# project_9.net
KiCad netlist of a schematic drawn in Altium Designer
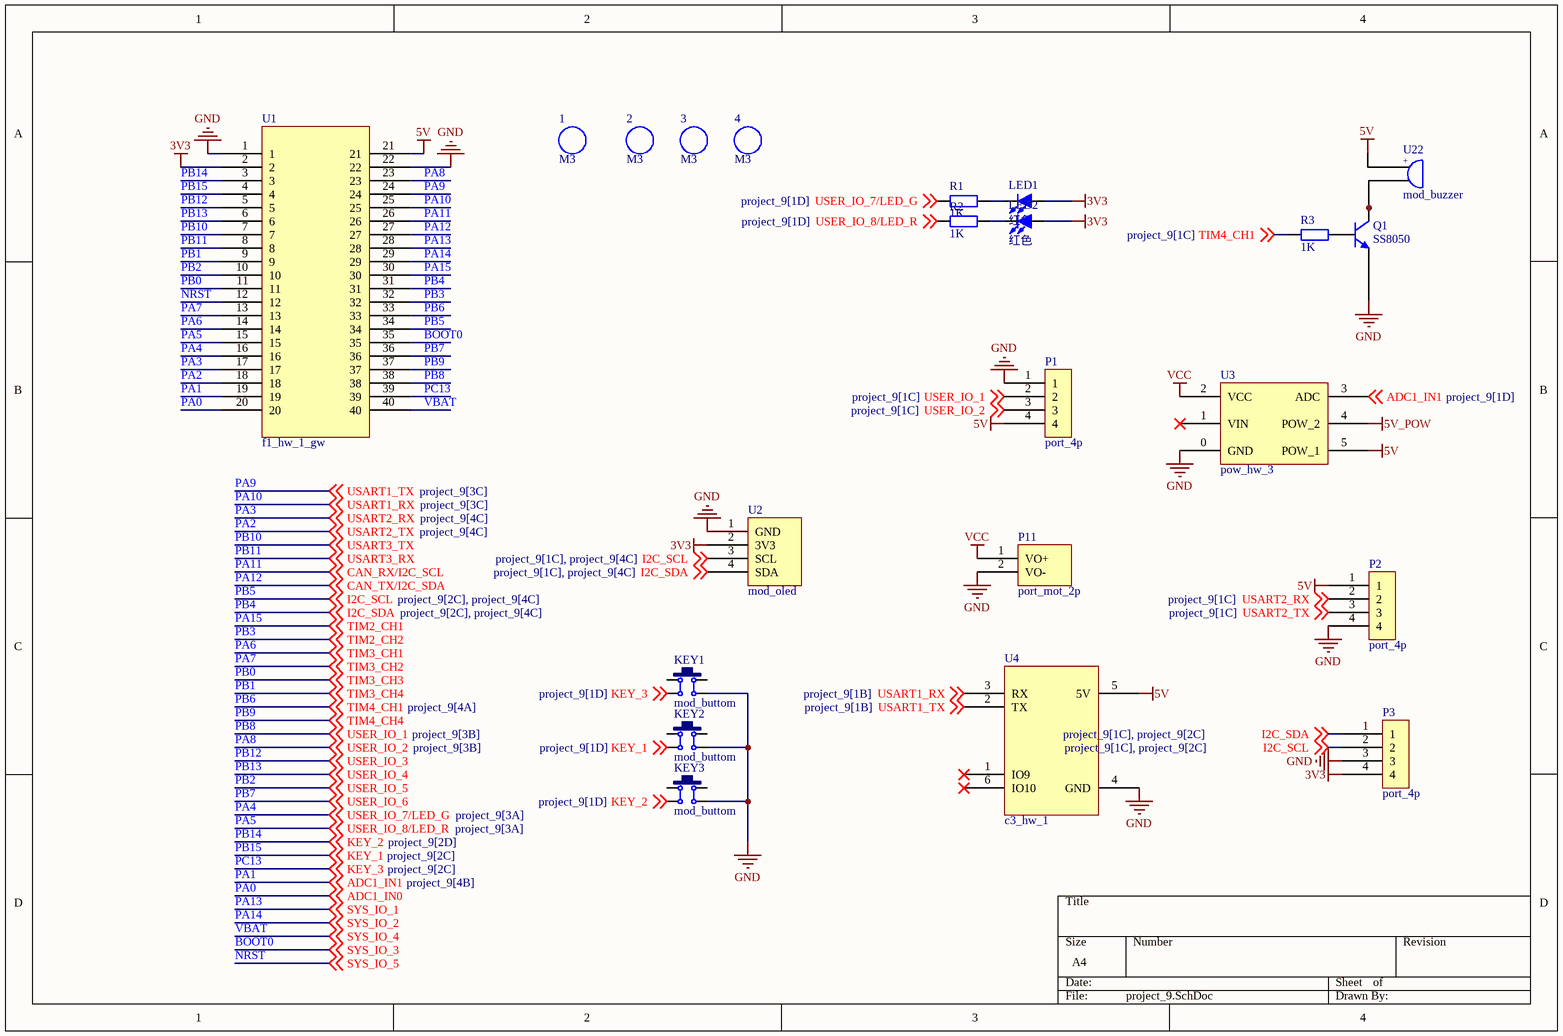
[diagram p0: project_9.SchDoc]

(export (version "E")
  (design (tool "Eeschema 10.0.6"))
  (components
    (comp (ref "1")
      (value "M3")
      (footprint "M3 125X200")
      (description "m3铜柱孔")
      (fields (field (name "版权归属") "源创客"))
      (libsource (lib "userLib") (part "prot_m3"))
    )
    (comp (ref "2")
      (value "M3")
      (footprint "M3 125X200")
      (description "m3铜柱孔")
      (fields (field (name "版权归属") "源创客"))
      (libsource (lib "userLib") (part "prot_m3"))
    )
    (comp (ref "3")
      (value "M3")
      (footprint "M3 125X200")
      (description "m3铜柱孔")
      (fields (field (name "版权归属") "源创客"))
      (libsource (lib "userLib") (part "prot_m3"))
    )
    (comp (ref "4")
      (value "M3")
      (footprint "M3 125X200")
      (description "m3铜柱孔")
      (fields (field (name "版权归属") "源创客"))
      (libsource (lib "userLib") (part "prot_m3"))
    )
    (comp (ref "KEY1")
      (value "mod_buttom")
      (footprint "MOD_BUTTOM")
      (description "6*6*4.3按键")
      (libsource (lib "userLib") (part "mod_buttom"))
    )
    (comp (ref "KEY2")
      (value "mod_buttom")
      (footprint "MOD_BUTTOM")
      (description "6*6*4.3按键")
      (libsource (lib "userLib") (part "mod_buttom"))
    )
    (comp (ref "KEY3")
      (value "mod_buttom")
      (footprint "MOD_BUTTOM")
      (description "6*6*4.3按键")
      (libsource (lib "userLib") (part "mod_buttom"))
    )
    (comp (ref "LED1")
      (value "红色")
      (footprint "LED 3MM-B")
      (description "插件LED")
      (fields (field (name "版权归属") "源创客"))
      (libsource (lib "userLib") (part "mod_LED"))
    )
    (comp (ref "LED2")
      (value "红色")
      (footprint "LED 3MM-B")
      (description "插件LED")
      (fields (field (name "版权归属") "源创客"))
      (libsource (lib "userLib") (part "mod_LED"))
    )
    (comp (ref "P1")
      (value "port_4p")
      (footprint "MOD_ECHO(XH2.54)")
      (description "4P模块接口")
      (libsource (lib "userLib") (part "port_4p"))
    )
    (comp (ref "P2")
      (value "port_4p")
      (footprint "MOD_RS485")
      (description "4P模块接口")
      (libsource (lib "userLib") (part "port_4p"))
    )
    (comp (ref "P3")
      (value "port_4p")
      (footprint "MOD_TEMP")
      (description "4P模块接口")
      (libsource (lib "userLib") (part "port_4p"))
    )
    (comp (ref "P11")
      (value "port_mot_2p")
      (footprint "XH2.54_2P")
      (description "开环直流电机接口\r\nXH2.54弯排针2p")
      (libsource (lib "userLib") (part "port_mot_2p"))
    )
    (comp (ref "Q1")
      (value "SS8050")
      (footprint "SOT23-3L")
      (description "高频放大-NPN型")
      (fields (field (name "版权归属") "源创客"))
      (libsource (lib "5.1-三极管") (part "8050-SMD"))
    )
    (comp (ref "R1")
      (value "1K")
      (footprint "R 0603_L")
      (description "贴片电阻")
      (fields (field (name "版权归属") "源创客"))
      (libsource (lib "3.1-电阻") (part "R"))
    )
    (comp (ref "R2")
      (value "1K")
      (footprint "R 0603_L")
      (description "贴片电阻")
      (fields (field (name "版权归属") "源创客"))
      (libsource (lib "3.1-电阻") (part "R"))
    )
    (comp (ref "R3")
      (value "1K")
      (footprint "R 0603_L")
      (description "贴片电阻")
      (fields (field (name "版权归属") "源创客"))
      (libsource (lib "3.1-电阻") (part "R"))
    )
    (comp (ref "U1")
      (value "f1_hw_1_gw")
      (footprint "F1_HW_1_GW")
      (libsource (lib "userLib") (part "f1_hw_1_gw"))
    )
    (comp (ref "U2")
      (value "mod_oled")
      (footprint "MOD_OLED")
      (description "oled模块\r\n4p排母")
      (libsource (lib "userLib") (part "mod_oled"))
    )
    (comp (ref "U3") (value "pow_hw_3") (footprint "POW_HW_3") (libsource (lib "userLib") (part "pow_hw_3")))
    (comp (ref "U4")
      (value "c3_hw_1")
      (footprint "C3_HW_1")
      (description "ESP32C3蓝牙模块\r\n6p排母")
      (libsource (lib "userLib") (part "c3_hw_1"))
    )
    (comp (ref "U22")
      (value "mod_buzzer")
      (footprint "MOD_BUZZER")
      (description "有源蜂鸣器")
      (libsource (lib "userLib") (part "mod_buzzer"))
    )
  )
  (nets
    (net (code "1") (name "3V3") (class "Default")
      (node (ref "LED1") (pin "1") (pinfunction "A_1") (pintype "passive"))
      (node (ref "LED2") (pin "1") (pinfunction "A_1") (pintype "passive"))
      (node (ref "P3") (pin "4") (pinfunction "4_4") (pintype "passive"))
      (node (ref "U1") (pin "2") (pinfunction "2_2") (pintype "passive"))
      (node (ref "U2") (pin "2") (pinfunction "3V3_2") (pintype "passive"))
    )
    (net (code "2") (name "5V") (class "Default")
      (node (ref "P1") (pin "4") (pinfunction "4_4") (pintype "passive"))
      (node (ref "P2") (pin "1") (pinfunction "1_1") (pintype "passive"))
      (node (ref "U1") (pin "21") (pinfunction "21_21") (pintype "passive"))
      (node (ref "U22") (pin "1") (pinfunction "1_1") (pintype "passive"))
      (node (ref "U3") (pin "5") (pinfunction "POW_1_5") (pintype "passive"))
      (node (ref "U4") (pin "5") (pinfunction "5V_5") (pintype "passive"))
    )
    (net (code "3") (name "5V_POW") (class "Default")
      (node (ref "U3") (pin "4") (pinfunction "POW_2_4") (pintype "passive"))
    )
    (net (code "4") (name "ADC1_IN0") (class "Default")
      (node (ref "U1") (pin "20") (pinfunction "20_20") (pintype "passive"))
    )
    (net (code "5") (name "ADC1_IN1") (class "Default")
      (node (ref "U1") (pin "19") (pinfunction "19_19") (pintype "passive"))
      (node (ref "U3") (pin "3") (pinfunction "ADC_3") (pintype "passive"))
    )
    (net (code "6") (name "CAN_RX{slash}I2C_SCL") (class "Default")
      (node (ref "U1") (pin "26") (pinfunction "26_26") (pintype "passive"))
    )
    (net (code "7") (name "CAN_TX{slash}I2C_SDA") (class "Default")
      (node (ref "U1") (pin "27") (pinfunction "27_27") (pintype "passive"))
    )
    (net (code "8") (name "GND") (class "Default")
      (node (ref "KEY1") (pin "3") (pinfunction "3_3") (pintype "passive"))
      (node (ref "KEY2") (pin "3") (pinfunction "3_3") (pintype "passive"))
      (node (ref "KEY3") (pin "3") (pinfunction "3_3") (pintype "passive"))
      (node (ref "P1") (pin "1") (pinfunction "1_1") (pintype "passive"))
      (node (ref "P11") (pin "2") (pinfunction "VO-_2") (pintype "passive"))
      (node (ref "P2") (pin "4") (pinfunction "4_4") (pintype "passive"))
      (node (ref "P3") (pin "3") (pinfunction "3_3") (pintype "passive"))
      (node (ref "Q1") (pin "2") (pinfunction "E_2") (pintype "passive"))
      (node (ref "U1") (pin "1") (pinfunction "1_1") (pintype "passive"))
      (node (ref "U1") (pin "22") (pinfunction "22_22") (pintype "passive"))
      (node (ref "U2") (pin "1") (pinfunction "GND_1") (pintype "passive"))
      (node (ref "U3") (pin "0") (pinfunction "GND_0") (pintype "passive"))
      (node (ref "U4") (pin "4") (pinfunction "GND_4") (pintype "passive"))
    )
    (net (code "9") (name "I2C_SCL") (class "Default")
      (node (ref "P3") (pin "2") (pinfunction "2_2") (pintype "passive"))
      (node (ref "U1") (pin "34") (pinfunction "34_34") (pintype "passive"))
      (node (ref "U2") (pin "3") (pinfunction "SCL_3") (pintype "passive"))
    )
    (net (code "10") (name "I2C_SDA") (class "Default")
      (node (ref "P3") (pin "1") (pinfunction "1_1") (pintype "passive"))
      (node (ref "U1") (pin "31") (pinfunction "31_31") (pintype "passive"))
      (node (ref "U2") (pin "4") (pinfunction "SDA_4") (pintype "passive"))
    )
    (net (code "11") (name "KEY_1") (class "Default")
      (node (ref "KEY2") (pin "4") (pinfunction "4_4") (pintype "passive"))
      (node (ref "U1") (pin "4") (pinfunction "4_4") (pintype "passive"))
    )
    (net (code "12") (name "KEY_2") (class "Default")
      (node (ref "KEY3") (pin "4") (pinfunction "4_4") (pintype "passive"))
      (node (ref "U1") (pin "3") (pinfunction "3_3") (pintype "passive"))
    )
    (net (code "13") (name "KEY_3") (class "Default")
      (node (ref "KEY1") (pin "4") (pinfunction "4_4") (pintype "passive"))
      (node (ref "U1") (pin "39") (pinfunction "39_39") (pintype "passive"))
    )
    (net (code "14") (name "Net-(LED1-K)") (class "Default")
      (node (ref "LED1") (pin "2") (pinfunction "K_2") (pintype "passive"))
      (node (ref "R1") (pin "2") (pinfunction "2_2") (pintype "passive"))
    )
    (net (code "15") (name "Net-(LED2-K)") (class "Default")
      (node (ref "LED2") (pin "2") (pinfunction "K_2") (pintype "passive"))
      (node (ref "R2") (pin "2") (pinfunction "2_2") (pintype "passive"))
    )
    (net (code "16") (name "Net-(Q1-B)") (class "Default")
      (node (ref "Q1") (pin "1") (pinfunction "B_1") (pintype "passive"))
      (node (ref "R3") (pin "2") (pinfunction "2_2") (pintype "passive"))
    )
    (net (code "17") (name "Net-(Q1-C)") (class "Default")
      (node (ref "Q1") (pin "3") (pinfunction "C_3") (pintype "passive"))
      (node (ref "U22") (pin "2") (pinfunction "2_2") (pintype "passive"))
    )
    (net (code "18") (name "SYS_IO_1") (class "Default")
      (node (ref "U1") (pin "28") (pinfunction "28_28") (pintype "passive"))
    )
    (net (code "19") (name "SYS_IO_2") (class "Default")
      (node (ref "U1") (pin "29") (pinfunction "29_29") (pintype "passive"))
    )
    (net (code "20") (name "SYS_IO_3") (class "Default")
      (node (ref "U1") (pin "35") (pinfunction "35_35") (pintype "passive"))
    )
    (net (code "21") (name "SYS_IO_4") (class "Default")
      (node (ref "U1") (pin "40") (pinfunction "40_40") (pintype "passive"))
    )
    (net (code "22") (name "SYS_IO_5") (class "Default")
      (node (ref "U1") (pin "12") (pinfunction "12_12") (pintype "passive"))
    )
    (net (code "23") (name "TIM2_CH1") (class "Default")
      (node (ref "U1") (pin "30") (pinfunction "30_30") (pintype "passive"))
    )
    (net (code "24") (name "TIM2_CH2") (class "Default")
      (node (ref "U1") (pin "32") (pinfunction "32_32") (pintype "passive"))
    )
    (net (code "25") (name "TIM3_CH1") (class "Default")
      (node (ref "U1") (pin "14") (pinfunction "14_14") (pintype "passive"))
    )
    (net (code "26") (name "TIM3_CH2") (class "Default")
      (node (ref "U1") (pin "13") (pinfunction "13_13") (pintype "passive"))
    )
    (net (code "27") (name "TIM3_CH3") (class "Default")
      (node (ref "U1") (pin "11") (pinfunction "11_11") (pintype "passive"))
    )
    (net (code "28") (name "TIM3_CH4") (class "Default")
      (node (ref "U1") (pin "9") (pinfunction "9_9") (pintype "passive"))
    )
    (net (code "29") (name "TIM4_CH1") (class "Default")
      (node (ref "R3") (pin "1") (pinfunction "1_1") (pintype "passive"))
      (node (ref "U1") (pin "33") (pinfunction "33_33") (pintype "passive"))
    )
    (net (code "30") (name "TIM4_CH4") (class "Default")
      (node (ref "U1") (pin "37") (pinfunction "37_37") (pintype "passive"))
    )
    (net (code "31") (name "USART1_RX") (class "Default")
      (node (ref "U1") (pin "25") (pinfunction "25_25") (pintype "passive"))
      (node (ref "U4") (pin "3") (pinfunction "RX_3") (pintype "passive"))
    )
    (net (code "32") (name "USART1_TX") (class "Default")
      (node (ref "U1") (pin "24") (pinfunction "24_24") (pintype "passive"))
      (node (ref "U4") (pin "2") (pinfunction "TX_2") (pintype "passive"))
    )
    (net (code "33") (name "USART2_RX") (class "Default")
      (node (ref "P2") (pin "2") (pinfunction "2_2") (pintype "passive"))
      (node (ref "U1") (pin "17") (pinfunction "17_17") (pintype "passive"))
    )
    (net (code "34") (name "USART2_TX") (class "Default")
      (node (ref "P2") (pin "3") (pinfunction "3_3") (pintype "passive"))
      (node (ref "U1") (pin "18") (pinfunction "18_18") (pintype "passive"))
    )
    (net (code "35") (name "USART3_RX") (class "Default")
      (node (ref "U1") (pin "8") (pinfunction "8_8") (pintype "passive"))
    )
    (net (code "36") (name "USART3_TX") (class "Default")
      (node (ref "U1") (pin "7") (pinfunction "7_7") (pintype "passive"))
    )
    (net (code "37") (name "USER_IO_1") (class "Default")
      (node (ref "P1") (pin "2") (pinfunction "2_2") (pintype "passive"))
      (node (ref "U1") (pin "38") (pinfunction "38_38") (pintype "passive"))
    )
    (net (code "38") (name "USER_IO_2") (class "Default")
      (node (ref "P1") (pin "3") (pinfunction "3_3") (pintype "passive"))
      (node (ref "U1") (pin "23") (pinfunction "23_23") (pintype "passive"))
    )
    (net (code "39") (name "USER_IO_3") (class "Default")
      (node (ref "U1") (pin "5") (pinfunction "5_5") (pintype "passive"))
    )
    (net (code "40") (name "USER_IO_4") (class "Default")
      (node (ref "U1") (pin "6") (pinfunction "6_6") (pintype "passive"))
    )
    (net (code "41") (name "USER_IO_5") (class "Default")
      (node (ref "U1") (pin "10") (pinfunction "10_10") (pintype "passive"))
    )
    (net (code "42") (name "USER_IO_6") (class "Default")
      (node (ref "U1") (pin "36") (pinfunction "36_36") (pintype "passive"))
    )
    (net (code "43") (name "USER_IO_7{slash}LED_G") (class "Default")
      (node (ref "R1") (pin "1") (pinfunction "1_1") (pintype "passive"))
      (node (ref "U1") (pin "16") (pinfunction "16_16") (pintype "passive"))
    )
    (net (code "44") (name "USER_IO_8{slash}LED_R") (class "Default")
      (node (ref "R2") (pin "1") (pinfunction "1_1") (pintype "passive"))
      (node (ref "U1") (pin "15") (pinfunction "15_15") (pintype "passive"))
    )
    (net (code "45") (name "VCC") (class "Default")
      (node (ref "P11") (pin "1") (pinfunction "VO+_1") (pintype "passive"))
      (node (ref "U3") (pin "2") (pinfunction "VCC_2") (pintype "passive"))
    )
    (net (code "46") (name "unconnected-(KEY1-Pad1)") (class "Default")
      (node (ref "KEY1") (pin "1") (pinfunction "1_1") (pintype "passive"))
    )
    (net (code "47") (name "unconnected-(KEY1-Pad2)") (class "Default")
      (node (ref "KEY1") (pin "2") (pinfunction "2_2") (pintype "passive"))
    )
    (net (code "48") (name "unconnected-(KEY2-Pad1)") (class "Default")
      (node (ref "KEY2") (pin "1") (pinfunction "1_1") (pintype "passive"))
    )
    (net (code "49") (name "unconnected-(KEY2-Pad2)") (class "Default")
      (node (ref "KEY2") (pin "2") (pinfunction "2_2") (pintype "passive"))
    )
    (net (code "50") (name "unconnected-(KEY3-Pad1)") (class "Default")
      (node (ref "KEY3") (pin "1") (pinfunction "1_1") (pintype "passive"))
    )
    (net (code "51") (name "unconnected-(KEY3-Pad2)") (class "Default")
      (node (ref "KEY3") (pin "2") (pinfunction "2_2") (pintype "passive"))
    )
    (net (code "52") (name "unconnected-(U3-VIN-Pad1)") (class "Default")
      (node (ref "U3") (pin "1") (pinfunction "VIN_1") (pintype "passive+no_connect"))
    )
    (net (code "53") (name "unconnected-(U4-IO9-Pad1)") (class "Default")
      (node (ref "U4") (pin "1") (pinfunction "IO9_1") (pintype "passive+no_connect"))
    )
    (net (code "54") (name "unconnected-(U4-IO10-Pad6)") (class "Default")
      (node (ref "U4") (pin "6") (pinfunction "IO10_6") (pintype "passive+no_connect"))
    )
  )
)
